# Power.net
KiCad netlist of a schematic drawn in Altium Designer
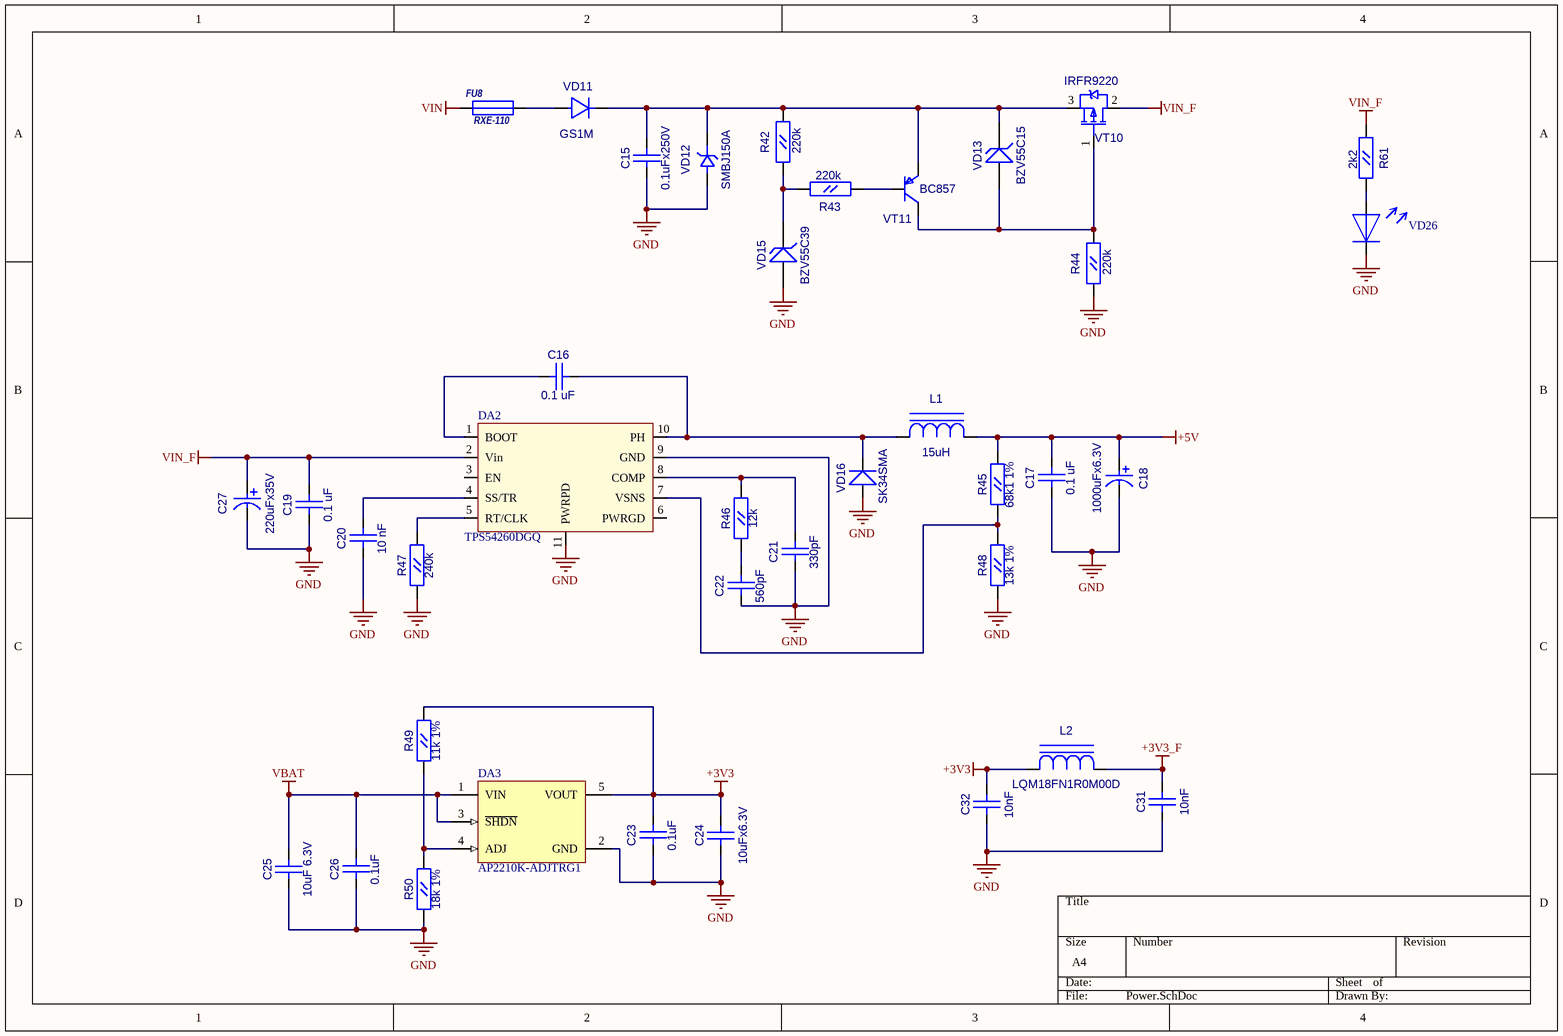
[diagram p0: Power.SchDoc]

(export (version "E")
  (design (tool "Eeschema 10.0.6"))
  (components
    (comp (ref "C15")
      (value "0.1uFx250V")
      (footprint "CC1206")
      (description "CC1206")
      (libsource (lib "gprs_modem_2") (part "CC1206"))
    )
    (comp (ref "C16")
      (value "0.1 uF")
      (footprint "CC0603")
      (description "CC0603")
      (libsource (lib "gprs_modem_2") (part "CC0603"))
    )
    (comp (ref "C17")
      (value "0.1 uF")
      (footprint "CC0603")
      (description "CC0603")
      (libsource (lib "gprs_modem_2") (part "CC0603"))
    )
    (comp (ref "C18")
      (value "1000uFx6.3V")
      (footprint "CC8X3.5")
      (description "CAP0.35")
      (libsource (lib "gprs_modem_2") (part "CAP0.35"))
    )
    (comp (ref "C19")
      (value "0.1 uF")
      (footprint "CC0603")
      (description "CC0603")
      (libsource (lib "gprs_modem_2") (part "CC0603"))
    )
    (comp (ref "C20")
      (value "10 nF")
      (footprint "CC0603")
      (description "CC0603")
      (libsource (lib "gprs_modem_2") (part "CC0603"))
    )
    (comp (ref "C21")
      (value "330pF")
      (footprint "CC0603")
      (description "CC0603")
      (libsource (lib "gprs_modem_2") (part "CC0603"))
    )
    (comp (ref "C22")
      (value "560pF")
      (footprint "CC0603")
      (description "CC0603")
      (libsource (lib "gprs_modem_2") (part "CC0603"))
    )
    (comp (ref "C23")
      (value "0.1uF")
      (footprint "CC0603")
      (description "CC0603")
      (libsource (lib "gprs_modem_2") (part "CC0603"))
    )
    (comp (ref "C24")
      (value "10uFx6.3V")
      (footprint "CC0805")
      (description "CC0805")
      (libsource (lib "gprs_modem_2") (part "CC0805"))
    )
    (comp (ref "C25")
      (value "10uF 6.3V")
      (footprint "CC0805")
      (description "CC0805")
      (libsource (lib "gprs_modem_2") (part "CC0805"))
    )
    (comp (ref "C26")
      (value "0.1uF")
      (footprint "CC0603")
      (description "CC0603")
      (libsource (lib "gprs_modem_2") (part "CC0603"))
    )
    (comp (ref "C27")
      (value "220uFx35V")
      (footprint "CC16X10_CAP0.5(1)(Primary)")
      (description "CAP0.5(1)")
      (libsource (lib "gprs_modem_2") (part "CAP0.5(1)"))
    )
    (comp (ref "C31")
      (value "10nF")
      (footprint "CC0603")
      (description "CC0603")
      (libsource (lib "gprs_modem_2") (part "CC0603"))
    )
    (comp (ref "C32")
      (value "10nF")
      (footprint "CC0603")
      (description "CC0603")
      (libsource (lib "gprs_modem_2") (part "CC0603"))
    )
    (comp (ref "DA2")
      (value "TPS54260DGQ")
      (footprint "S-PDSO-G10")
      (libsource (lib "gprs_modem_2") (part "TPS54260DGQ"))
    )
    (comp (ref "DA3")
      (value "AP2210K-ADJTRG1")
      (footprint "SOT23-5")
      (fields (field (name "PUBLISHER") "Altium Limited"))
      (libsource (lib "gprs_modem_2") (part "MCP1824T-ADJE/OT"))
    )
    (comp (ref "FU8")
      (value "RXE-110")
      (footprint "RXE-110")
      (libsource (lib "gprs_modem_2") (part "RXE-110"))
    )
    (comp (ref "L1")
      (value "15uH")
      (footprint "SDR0805")
      (description "SDR0805")
      (libsource (lib "gprs_modem_2") (part "SDR0805"))
    )
    (comp (ref "L2")
      (value "LQM18FN1R0M00D")
      (footprint "L0603")
      (description "L0603")
      (libsource (lib "gprs_modem_2") (part "L0603"))
    )
    (comp (ref "R42")
      (value "220k")
      (footprint "RC0603")
      (description "RC0603")
      (libsource (lib "gprs_modem_2") (part "RC0603"))
    )
    (comp (ref "R43")
      (value "220k")
      (footprint "RC0603")
      (description "RC0603")
      (libsource (lib "gprs_modem_2") (part "RC0603"))
    )
    (comp (ref "R44")
      (value "220k")
      (footprint "RC0603")
      (description "RC0603")
      (libsource (lib "gprs_modem_2") (part "RC0603"))
    )
    (comp (ref "R45")
      (value "68k1 1%")
      (footprint "RC0603")
      (description "RC0603")
      (libsource (lib "gprs_modem_2") (part "RC0603"))
    )
    (comp (ref "R46")
      (value "12k")
      (footprint "RC0603")
      (description "RC0603")
      (libsource (lib "gprs_modem_2") (part "RC0603"))
    )
    (comp (ref "R47")
      (value "240k")
      (footprint "RC0603")
      (description "RC0603")
      (libsource (lib "gprs_modem_2") (part "RC0603"))
    )
    (comp (ref "R48")
      (value "13k 1%")
      (footprint "RC0603")
      (description "RC0603")
      (libsource (lib "gprs_modem_2") (part "RC0603"))
    )
    (comp (ref "R49")
      (value "11k 1%")
      (footprint "RC0603")
      (description "RC0603")
      (libsource (lib "gprs_modem_2") (part "RC0603"))
    )
    (comp (ref "R50")
      (value "18k 1%")
      (footprint "RC0603")
      (description "RC0603")
      (libsource (lib "gprs_modem_2") (part "RC0603"))
    )
    (comp (ref "R61")
      (value "2k2")
      (footprint "RC0603")
      (description "RC0603")
      (libsource (lib "gprs_modem_2") (part "RC0603"))
    )
    (comp (ref "VD11") (value "GS1M") (footprint "SMA") (libsource (lib "gprs_modem_2") (part "GS1M")))
    (comp (ref "VD12")
      (value "SMBJ150A")
      (footprint "SMB")
      (description "SMBJ")
      (libsource (lib "gprs_modem_2") (part "SMBJ"))
    )
    (comp (ref "VD13")
      (value "BZV55C15")
      (footprint "SOD-80")
      (description "Zener Voltage Regulator Diode")
      (libsource (lib "gprs_modem_2") (part "BZV55C12"))
    )
    (comp (ref "VD15")
      (value "BZV55C39")
      (footprint "SOD-80")
      (description "Zener Voltage Regulator Diode")
      (libsource (lib "gprs_modem_2") (part "BZV55C12"))
    )
    (comp (ref "VD16")
      (value "SK34SMA")
      (footprint "SMA")
      (description "Schottky Rectifier")
      (libsource (lib "gprs_modem") (part "SK34SMA"))
    )
    (comp (ref "VD26")
      (value "LED_0805")
      (footprint "LED0805")
      (libsource (lib "gprs_modem_2") (part "LED_0805"))
    )
    (comp (ref "VT10")
      (value "IRFR9220")
      (footprint "D-PAK(TO-252AA)")
      (description "HEXFET Power MOSFET")
      (libsource (lib "gprs_modem_2") (part "IRFR9220"))
    )
    (comp (ref "VT11")
      (value "BC857")
      (footprint "SOT-23(123)")
      (description "PNP 100ma transistor")
      (libsource (lib "gprs_modem_2") (part "BC857B"))
    )
  )
  (nets
    (net (code "1") (name "+3V3") (class "Default")
      (node (ref "C23") (pin "1") (pinfunction "A_1") (pintype "passive"))
      (node (ref "C24") (pin "2") (pinfunction "B_2") (pintype "passive"))
      (node (ref "C32") (pin "2") (pinfunction "B_2") (pintype "passive"))
      (node (ref "DA3") (pin "5") (pinfunction "VOUT_5") (pintype "power_in"))
      (node (ref "L2") (pin "1") (pinfunction "A_1") (pintype "passive"))
      (node (ref "R49") (pin "2") (pinfunction "B_2") (pintype "passive"))
    )
    (net (code "2") (name "+3V3_F") (class "Default")
      (node (ref "C31") (pin "2") (pinfunction "B_2") (pintype "passive"))
      (node (ref "L2") (pin "2") (pinfunction "C_2") (pintype "passive"))
    )
    (net (code "3") (name "+5V") (class "Default")
      (node (ref "C17") (pin "1") (pinfunction "A_1") (pintype "passive"))
      (node (ref "C18") (pin "1") (pintype "passive"))
      (node (ref "L1") (pin "2") (pinfunction "A_2") (pintype "passive"))
      (node (ref "R45") (pin "2") (pinfunction "B_2") (pintype "passive"))
    )
    (net (code "4") (name "GND") (class "Default")
      (node (ref "C15") (pin "1") (pinfunction "A_1") (pintype "passive"))
      (node (ref "C17") (pin "2") (pinfunction "B_2") (pintype "passive"))
      (node (ref "C18") (pin "2") (pintype "passive"))
      (node (ref "C19") (pin "2") (pinfunction "B_2") (pintype "passive"))
      (node (ref "C20") (pin "2") (pinfunction "B_2") (pintype "passive"))
      (node (ref "C21") (pin "2") (pinfunction "B_2") (pintype "passive"))
      (node (ref "C22") (pin "2") (pinfunction "B_2") (pintype "passive"))
      (node (ref "C23") (pin "2") (pinfunction "B_2") (pintype "passive"))
      (node (ref "C24") (pin "1") (pinfunction "A_1") (pintype "passive"))
      (node (ref "C25") (pin "1") (pinfunction "A_1") (pintype "passive"))
      (node (ref "C26") (pin "2") (pinfunction "B_2") (pintype "passive"))
      (node (ref "C27") (pin "1") (pintype "passive"))
      (node (ref "C31") (pin "1") (pinfunction "A_1") (pintype "passive"))
      (node (ref "C32") (pin "1") (pinfunction "A_1") (pintype "passive"))
      (node (ref "DA2") (pin "11") (pinfunction "PWRPD_11") (pintype "passive"))
      (node (ref "DA2") (pin "9") (pinfunction "GND_9") (pintype "passive"))
      (node (ref "DA3") (pin "2") (pinfunction "GND_2") (pintype "power_in"))
      (node (ref "R44") (pin "1") (pinfunction "A_1") (pintype "passive"))
      (node (ref "R47") (pin "1") (pinfunction "A_1") (pintype "passive"))
      (node (ref "R48") (pin "1") (pinfunction "A_1") (pintype "passive"))
      (node (ref "R50") (pin "1") (pinfunction "A_1") (pintype "passive"))
      (node (ref "VD12") (pin "1") (pinfunction "A_1") (pintype "passive"))
      (node (ref "VD15") (pin "1") (pinfunction "A_1") (pintype "passive"))
      (node (ref "VD16") (pin "1") (pinfunction "A_1") (pintype "passive"))
      (node (ref "VD26") (pin "2") (pintype "passive"))
    )
    (net (code "5") (name "Net-(C15-B)") (class "Default")
      (node (ref "C15") (pin "2") (pinfunction "B_2") (pintype "passive"))
      (node (ref "R42") (pin "2") (pinfunction "B_2") (pintype "passive"))
      (node (ref "VD11") (pin "2") (pinfunction "K_2") (pintype "passive"))
      (node (ref "VD12") (pin "2") (pinfunction "K_2") (pintype "passive"))
      (node (ref "VD13") (pin "2") (pintype "passive"))
      (node (ref "VT10") (pin "3") (pinfunction "S_3") (pintype "passive"))
      (node (ref "VT11") (pin "2") (pinfunction "E_2") (pintype "passive"))
    )
    (net (code "6") (name "Net-(C16-A)") (class "Default")
      (node (ref "C16") (pin "1") (pinfunction "A_1") (pintype "passive"))
      (node (ref "DA2") (pin "10") (pinfunction "PH_10") (pintype "passive"))
      (node (ref "L1") (pin "1") (pinfunction "C_1") (pintype "passive"))
      (node (ref "VD16") (pin "2") (pinfunction "K_2") (pintype "passive"))
    )
    (net (code "7") (name "Net-(C16-B)") (class "Default")
      (node (ref "C16") (pin "2") (pinfunction "B_2") (pintype "passive"))
      (node (ref "DA2") (pin "1") (pinfunction "BOOT_1") (pintype "passive"))
    )
    (net (code "8") (name "Net-(C20-A)") (class "Default")
      (node (ref "C20") (pin "1") (pinfunction "A_1") (pintype "passive"))
      (node (ref "DA2") (pin "4") (pinfunction "SS/TR_4") (pintype "passive"))
    )
    (net (code "9") (name "Net-(C21-A)") (class "Default")
      (node (ref "C21") (pin "1") (pinfunction "A_1") (pintype "passive"))
      (node (ref "DA2") (pin "8") (pinfunction "COMP_8") (pintype "passive"))
      (node (ref "R46") (pin "2") (pinfunction "B_2") (pintype "passive"))
    )
    (net (code "10") (name "Net-(C22-A)") (class "Default")
      (node (ref "C22") (pin "1") (pinfunction "A_1") (pintype "passive"))
      (node (ref "R46") (pin "1") (pinfunction "A_1") (pintype "passive"))
    )
    (net (code "11") (name "Net-(DA2-RT{slash}CLK)") (class "Default")
      (node (ref "DA2") (pin "5") (pinfunction "RT/CLK_5") (pintype "passive"))
      (node (ref "R47") (pin "2") (pinfunction "B_2") (pintype "passive"))
    )
    (net (code "12") (name "Net-(DA2-VSNS)") (class "Default")
      (node (ref "DA2") (pin "7") (pinfunction "VSNS_7") (pintype "passive"))
      (node (ref "R45") (pin "1") (pinfunction "A_1") (pintype "passive"))
      (node (ref "R48") (pin "2") (pinfunction "B_2") (pintype "passive"))
    )
    (net (code "13") (name "Net-(DA3-ADJ)") (class "Default")
      (node (ref "DA3") (pin "4") (pinfunction "ADJ_4") (pintype "input"))
      (node (ref "R49") (pin "1") (pinfunction "A_1") (pintype "passive"))
      (node (ref "R50") (pin "2") (pinfunction "B_2") (pintype "passive"))
    )
    (net (code "14") (name "Net-(R42-A)") (class "Default")
      (node (ref "R42") (pin "1") (pinfunction "A_1") (pintype "passive"))
      (node (ref "R43") (pin "2") (pinfunction "B_2") (pintype "passive"))
      (node (ref "VD15") (pin "2") (pintype "passive"))
    )
    (net (code "15") (name "Net-(R43-A)") (class "Default")
      (node (ref "R43") (pin "1") (pinfunction "A_1") (pintype "passive"))
      (node (ref "VT11") (pin "1") (pinfunction "B_1") (pintype "passive"))
    )
    (net (code "16") (name "Net-(R44-B)") (class "Default")
      (node (ref "R44") (pin "2") (pinfunction "B_2") (pintype "passive"))
      (node (ref "VD13") (pin "1") (pinfunction "A_1") (pintype "passive"))
      (node (ref "VT10") (pin "1") (pinfunction "G_1") (pintype "passive"))
      (node (ref "VT11") (pin "3") (pinfunction "C_3") (pintype "passive"))
    )
    (net (code "17") (name "Net-(R61-B)") (class "Default")
      (node (ref "R61") (pin "2") (pinfunction "B_2") (pintype "passive"))
      (node (ref "VD26") (pin "1") (pintype "passive"))
    )
    (net (code "18") (name "Net-(VD11-A)") (class "Default")
      (node (ref "FU8") (pin "2") (pintype "passive"))
      (node (ref "VD11") (pin "1") (pinfunction "A_1") (pintype "passive"))
    )
    (net (code "19") (name "VBAT") (class "Default")
      (node (ref "C25") (pin "2") (pinfunction "B_2") (pintype "passive"))
      (node (ref "C26") (pin "1") (pinfunction "A_1") (pintype "passive"))
      (node (ref "DA3") (pin "1") (pinfunction "VIN_1") (pintype "power_in"))
      (node (ref "DA3") (pin "3") (pinfunction "~{SHDN}_3") (pintype "input"))
    )
    (net (code "20") (name "VIN") (class "Default") (node (ref "FU8") (pin "1") (pintype "passive")))
    (net (code "21") (name "VIN_F") (class "Default")
      (node (ref "C19") (pin "1") (pinfunction "A_1") (pintype "passive"))
      (node (ref "C27") (pin "2") (pintype "passive"))
      (node (ref "DA2") (pin "2") (pinfunction "Vin_2") (pintype "passive"))
      (node (ref "R61") (pin "1") (pinfunction "A_1") (pintype "passive"))
      (node (ref "VT10") (pin "2") (pinfunction "D_2") (pintype "passive"))
    )
    (net (code "22") (name "unconnected-(DA2-EN-Pad3)") (class "Default")
      (node (ref "DA2") (pin "3") (pinfunction "EN_3") (pintype "passive"))
    )
    (net (code "23") (name "unconnected-(DA2-PWRGD-Pad6)") (class "Default")
      (node (ref "DA2") (pin "6") (pinfunction "PWRGD_6") (pintype "passive"))
    )
  )
)
